# Monitoring_IC.net
KiCad netlist of a schematic drawn in Altium Designer
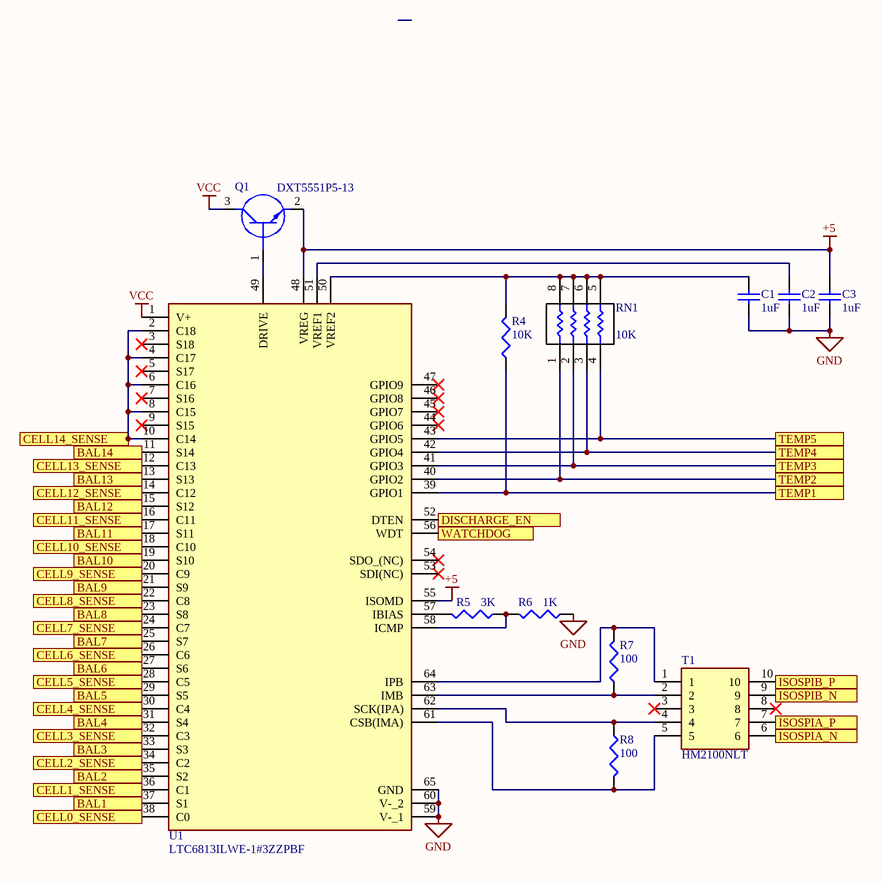
[diagram p0: Monitoring IC.SchDoc]

(export (version "E")
  (design (tool "Eeschema 10.0.6"))
  (components
    (comp (ref "C1")
      (value "1uF")
      (footprint "6-0805_N")
      (description "Capacitor")
      (fields (field (name "Comment") "Cap") (field (name "PUBLISHER") "Altium Limited"))
      (libsource (lib "Miscellaneous Devices") (part "Cap"))
    )
    (comp (ref "C2")
      (value "1uF")
      (footprint "6-0805_N")
      (description "Capacitor")
      (fields (field (name "Comment") "Cap") (field (name "PUBLISHER") "Altium Limited"))
      (libsource (lib "Miscellaneous Devices") (part "Cap"))
    )
    (comp (ref "C3")
      (value "1uF")
      (footprint "6-0805_N")
      (description "Capacitor")
      (fields (field (name "Comment") "Cap") (field (name "PUBLISHER") "Altium Limited"))
      (libsource (lib "Miscellaneous Devices") (part "Cap"))
    )
    (comp (ref "Q1")
      (value "DXT5551P5-13")
      (footprint "BMS Slave Device R1:DXT5551P513")
      (description "Transistor BJT NPN")
      (fields (field (name "MOUSER PART NUMBER") "522-DXT5551P5-13"))
      (libsource (lib "BMS Slave Device R1") (part "DXT5551P5-13"))
    )
    (comp (ref "R4")
      (value "10K")
      (footprint "J1-0603")
      (description "Resistor")
      (fields (field (name "Comment") "Res3") (field (name "PUBLISHER") "Altium Limited"))
      (libsource (lib "Miscellaneous Devices") (part "Res3"))
    )
    (comp (ref "R5")
      (value "3K")
      (footprint "J1-0603")
      (description "Resistor")
      (fields (field (name "Comment") "Res3") (field (name "PUBLISHER") "Altium Limited"))
      (libsource (lib "Miscellaneous Devices") (part "Res3"))
    )
    (comp (ref "R6")
      (value "1K")
      (footprint "J1-0603")
      (description "Resistor")
      (fields (field (name "Comment") "Res3") (field (name "PUBLISHER") "Altium Limited"))
      (libsource (lib "Miscellaneous Devices") (part "Res3"))
    )
    (comp (ref "R7")
      (value "100")
      (footprint "J1-0603")
      (description "Resistor")
      (fields (field (name "Comment") "Res3") (field (name "PUBLISHER") "Altium Limited"))
      (libsource (lib "Miscellaneous Devices") (part "Res3"))
    )
    (comp (ref "R8")
      (value "100")
      (footprint "J1-0603")
      (description "Resistor")
      (fields (field (name "Comment") "Res3") (field (name "PUBLISHER") "Altium Limited"))
      (libsource (lib "Miscellaneous Devices") (part "Res3"))
    )
    (comp (ref "RN1")
      (value "10K")
      (footprint "YC164")
      (description "Isolated Resistor Network")
      (fields (field (name "Comment") "Res Array") (field (name "PUBLISHER") "Altium Limited"))
      (libsource (lib "BMS Slave Device R1") (part "Res Array"))
    )
    (comp (ref "T1")
      (value "HM2100NLT")
      (footprint "HM2100NLT")
      (description "Transformer")
      (fields (field (name "MOUSER PART NUMBER") "673-HM2100NLT"))
      (libsource (lib "BMS Slave Device R1") (part "HM2100NLT"))
    )
    (comp (ref "U1")
      (value "LTC6813ILWE-1#3ZZPBF")
      (footprint "BMS Slave Device R1:QFP50P1200X1200X120-65N")
      (description "Integrated Circuit")
      (fields (field (name "MOUSER PART NUMBER") "584-6813ILWE13ZZPBF"))
      (libsource (lib "BMS Slave Device R1") (part "LTC6813ILWE-1#3ZZPBF"))
    )
  )
  (nets
    (net (code "1") (name "+5") (class "Default")
      (node (ref "C3") (pin "2") (pinfunction "2_2") (pintype "passive"))
      (node (ref "Q1") (pin "2") (pinfunction "E_2") (pintype "passive"))
      (node (ref "U1") (pin "48") (pinfunction "VREG_48") (pintype "passive"))
      (node (ref "U1") (pin "55") (pinfunction "ISOMD_55") (pintype "passive"))
    )
    (net (code "2") (name "/BAL1") (class "Default")
      (node (ref "U1") (pin "37") (pinfunction "S1_37") (pintype "passive"))
    )
    (net (code "3") (name "/BAL2") (class "Default")
      (node (ref "U1") (pin "35") (pinfunction "S2_35") (pintype "passive"))
    )
    (net (code "4") (name "/BAL3") (class "Default")
      (node (ref "U1") (pin "33") (pinfunction "S3_33") (pintype "passive"))
    )
    (net (code "5") (name "/BAL4") (class "Default")
      (node (ref "U1") (pin "31") (pinfunction "S4_31") (pintype "passive"))
    )
    (net (code "6") (name "/BAL5") (class "Default")
      (node (ref "U1") (pin "29") (pinfunction "S5_29") (pintype "passive"))
    )
    (net (code "7") (name "/BAL6") (class "Default")
      (node (ref "U1") (pin "27") (pinfunction "S6_27") (pintype "passive"))
    )
    (net (code "8") (name "/BAL7") (class "Default")
      (node (ref "U1") (pin "25") (pinfunction "S7_25") (pintype "passive"))
    )
    (net (code "9") (name "/BAL8") (class "Default")
      (node (ref "U1") (pin "23") (pinfunction "S8_23") (pintype "passive"))
    )
    (net (code "10") (name "/BAL9") (class "Default")
      (node (ref "U1") (pin "21") (pinfunction "S9_21") (pintype "passive"))
    )
    (net (code "11") (name "/BAL10") (class "Default")
      (node (ref "U1") (pin "19") (pinfunction "S10_19") (pintype "passive"))
    )
    (net (code "12") (name "/BAL11") (class "Default")
      (node (ref "U1") (pin "17") (pinfunction "S11_17") (pintype "passive"))
    )
    (net (code "13") (name "/BAL12") (class "Default")
      (node (ref "U1") (pin "15") (pinfunction "S12_15") (pintype "passive"))
    )
    (net (code "14") (name "/BAL13") (class "Default")
      (node (ref "U1") (pin "13") (pinfunction "S13_13") (pintype "passive"))
    )
    (net (code "15") (name "/BAL14") (class "Default")
      (node (ref "U1") (pin "11") (pinfunction "S14_11") (pintype "passive"))
    )
    (net (code "16") (name "/CELL0_SENSE") (class "Default")
      (node (ref "U1") (pin "38") (pinfunction "C0_38") (pintype "passive"))
    )
    (net (code "17") (name "/CELL1_SENSE") (class "Default")
      (node (ref "U1") (pin "36") (pinfunction "C1_36") (pintype "passive"))
    )
    (net (code "18") (name "/CELL2_SENSE") (class "Default")
      (node (ref "U1") (pin "34") (pinfunction "C2_34") (pintype "passive"))
    )
    (net (code "19") (name "/CELL3_SENSE") (class "Default")
      (node (ref "U1") (pin "32") (pinfunction "C3_32") (pintype "passive"))
    )
    (net (code "20") (name "/CELL4_SENSE") (class "Default")
      (node (ref "U1") (pin "30") (pinfunction "C4_30") (pintype "passive"))
    )
    (net (code "21") (name "/CELL5_SENSE") (class "Default")
      (node (ref "U1") (pin "28") (pinfunction "C5_28") (pintype "passive"))
    )
    (net (code "22") (name "/CELL6_SENSE") (class "Default")
      (node (ref "U1") (pin "26") (pinfunction "C6_26") (pintype "passive"))
    )
    (net (code "23") (name "/CELL7_SENSE") (class "Default")
      (node (ref "U1") (pin "24") (pinfunction "C7_24") (pintype "passive"))
    )
    (net (code "24") (name "/CELL8_SENSE") (class "Default")
      (node (ref "U1") (pin "22") (pinfunction "C8_22") (pintype "passive"))
    )
    (net (code "25") (name "/CELL9_SENSE") (class "Default")
      (node (ref "U1") (pin "20") (pinfunction "C9_20") (pintype "passive"))
    )
    (net (code "26") (name "/CELL10_SENSE") (class "Default")
      (node (ref "U1") (pin "18") (pinfunction "C10_18") (pintype "passive"))
    )
    (net (code "27") (name "/CELL11_SENSE") (class "Default")
      (node (ref "U1") (pin "16") (pinfunction "C11_16") (pintype "passive"))
    )
    (net (code "28") (name "/CELL12_SENSE") (class "Default")
      (node (ref "U1") (pin "14") (pinfunction "C12_14") (pintype "passive"))
    )
    (net (code "29") (name "/CELL13_SENSE") (class "Default")
      (node (ref "U1") (pin "12") (pinfunction "C13_12") (pintype "passive"))
    )
    (net (code "30") (name "/CELL14_SENSE") (class "Default")
      (node (ref "U1") (pin "10") (pinfunction "C14_10") (pintype "passive"))
      (node (ref "U1") (pin "2") (pinfunction "C18_2") (pintype "passive"))
      (node (ref "U1") (pin "4") (pinfunction "C17_4") (pintype "passive"))
      (node (ref "U1") (pin "6") (pinfunction "C16_6") (pintype "passive"))
      (node (ref "U1") (pin "8") (pinfunction "C15_8") (pintype "passive"))
    )
    (net (code "31") (name "/DISCHARGE_EN") (class "Default")
      (node (ref "U1") (pin "52") (pinfunction "DTEN_52") (pintype "passive"))
    )
    (net (code "32") (name "/ISOSPIA_N") (class "Default")
      (node (ref "T1") (pin "6") (pinfunction "6_6") (pintype "passive"))
    )
    (net (code "33") (name "/ISOSPIA_P") (class "Default")
      (node (ref "T1") (pin "7") (pinfunction "7_7") (pintype "passive"))
    )
    (net (code "34") (name "/ISOSPIB_N") (class "Default")
      (node (ref "T1") (pin "9") (pinfunction "9_9") (pintype "passive"))
    )
    (net (code "35") (name "/ISOSPIB_P") (class "Default")
      (node (ref "T1") (pin "10") (pinfunction "10_10") (pintype "passive"))
    )
    (net (code "36") (name "/TEMP1") (class "Default")
      (node (ref "R4") (pin "1") (pinfunction "1_1") (pintype "passive"))
      (node (ref "U1") (pin "39") (pinfunction "GPIO1_39") (pintype "passive"))
    )
    (net (code "37") (name "/TEMP2") (class "Default")
      (node (ref "RN1") (pin "1") (pinfunction "1_1") (pintype "passive"))
      (node (ref "U1") (pin "40") (pinfunction "GPIO2_40") (pintype "passive"))
    )
    (net (code "38") (name "/TEMP3") (class "Default")
      (node (ref "RN1") (pin "2") (pinfunction "2_2") (pintype "passive"))
      (node (ref "U1") (pin "41") (pinfunction "GPIO3_41") (pintype "passive"))
    )
    (net (code "39") (name "/TEMP4") (class "Default")
      (node (ref "RN1") (pin "3") (pinfunction "3_3") (pintype "passive"))
      (node (ref "U1") (pin "42") (pinfunction "GPIO4_42") (pintype "passive"))
    )
    (net (code "40") (name "/TEMP5") (class "Default")
      (node (ref "RN1") (pin "4") (pinfunction "4_4") (pintype "passive"))
      (node (ref "U1") (pin "43") (pinfunction "GPIO5_43") (pintype "passive"))
    )
    (net (code "41") (name "/WATCHDOG") (class "Default")
      (node (ref "U1") (pin "56") (pinfunction "WDT_56") (pintype "passive"))
    )
    (net (code "42") (name "GND") (class "Default")
      (node (ref "C1") (pin "1") (pinfunction "1_1") (pintype "passive"))
      (node (ref "C2") (pin "1") (pinfunction "1_1") (pintype "passive"))
      (node (ref "C3") (pin "1") (pinfunction "1_1") (pintype "passive"))
      (node (ref "R6") (pin "1") (pinfunction "1_1") (pintype "passive"))
      (node (ref "U1") (pin "59") (pinfunction "V-_1_59") (pintype "passive"))
      (node (ref "U1") (pin "60") (pinfunction "V-_2_60") (pintype "passive"))
      (node (ref "U1") (pin "65") (pinfunction "GND_65") (pintype "passive"))
    )
    (net (code "43") (name "Net-(Q1-B)") (class "Default")
      (node (ref "Q1") (pin "1") (pinfunction "B_1") (pintype "passive"))
      (node (ref "U1") (pin "49") (pinfunction "DRIVE_49") (pintype "passive"))
    )
    (net (code "44") (name "Net-(U1-CSB(IMA))") (class "Default")
      (node (ref "R8") (pin "2") (pinfunction "2_2") (pintype "passive"))
      (node (ref "T1") (pin "5") (pinfunction "5_5") (pintype "passive"))
      (node (ref "U1") (pin "61") (pinfunction "CSB(IMA)_61") (pintype "passive"))
    )
    (net (code "45") (name "Net-(U1-IBIAS)") (class "Default")
      (node (ref "R5") (pin "2") (pinfunction "2_2") (pintype "passive"))
      (node (ref "U1") (pin "57") (pinfunction "IBIAS_57") (pintype "passive"))
    )
    (net (code "46") (name "Net-(U1-ICMP)") (class "Default")
      (node (ref "R5") (pin "1") (pinfunction "1_1") (pintype "passive"))
      (node (ref "R6") (pin "2") (pinfunction "2_2") (pintype "passive"))
      (node (ref "U1") (pin "58") (pinfunction "ICMP_58") (pintype "passive"))
    )
    (net (code "47") (name "Net-(U1-IMB)") (class "Default")
      (node (ref "R7") (pin "1") (pinfunction "1_1") (pintype "passive"))
      (node (ref "T1") (pin "2") (pinfunction "2_2") (pintype "passive"))
      (node (ref "U1") (pin "63") (pinfunction "IMB_63") (pintype "passive"))
    )
    (net (code "48") (name "Net-(U1-IPB)") (class "Default")
      (node (ref "R7") (pin "2") (pinfunction "2_2") (pintype "passive"))
      (node (ref "T1") (pin "1") (pinfunction "1_1") (pintype "passive"))
      (node (ref "U1") (pin "64") (pinfunction "IPB_64") (pintype "passive"))
    )
    (net (code "49") (name "Net-(U1-SCK(IPA))") (class "Default")
      (node (ref "R8") (pin "1") (pinfunction "1_1") (pintype "passive"))
      (node (ref "T1") (pin "4") (pinfunction "4_4") (pintype "passive"))
      (node (ref "U1") (pin "62") (pinfunction "SCK(IPA)_62") (pintype "passive"))
    )
    (net (code "50") (name "Net-(U1-VREF1)") (class "Default")
      (node (ref "C2") (pin "2") (pinfunction "2_2") (pintype "passive"))
      (node (ref "U1") (pin "51") (pinfunction "VREF1_51") (pintype "passive"))
    )
    (net (code "51") (name "Net-(U1-VREF2)") (class "Default")
      (node (ref "C1") (pin "2") (pinfunction "2_2") (pintype "passive"))
      (node (ref "R4") (pin "2") (pinfunction "2_2") (pintype "passive"))
      (node (ref "RN1") (pin "5") (pinfunction "5_5") (pintype "passive"))
      (node (ref "RN1") (pin "6") (pinfunction "6_6") (pintype "passive"))
      (node (ref "RN1") (pin "7") (pinfunction "7_7") (pintype "passive"))
      (node (ref "RN1") (pin "8") (pinfunction "8_8") (pintype "passive"))
      (node (ref "U1") (pin "50") (pinfunction "VREF2_50") (pintype "passive"))
    )
    (net (code "52") (name "VCC") (class "Default")
      (node (ref "Q1") (pin "3") (pinfunction "C_3") (pintype "passive"))
      (node (ref "U1") (pin "1") (pinfunction "V+_1") (pintype "passive"))
    )
    (net (code "53") (name "unconnected-(T1-Pad3)") (class "Default")
      (node (ref "T1") (pin "3") (pinfunction "3_3") (pintype "passive+no_connect"))
    )
    (net (code "54") (name "unconnected-(T1-Pad8)") (class "Default")
      (node (ref "T1") (pin "8") (pinfunction "8_8") (pintype "passive+no_connect"))
    )
    (net (code "55") (name "unconnected-(U1-GPIO6-Pad44)") (class "Default")
      (node (ref "U1") (pin "44") (pinfunction "GPIO6_44") (pintype "passive+no_connect"))
    )
    (net (code "56") (name "unconnected-(U1-GPIO7-Pad45)") (class "Default")
      (node (ref "U1") (pin "45") (pinfunction "GPIO7_45") (pintype "passive+no_connect"))
    )
    (net (code "57") (name "unconnected-(U1-GPIO8-Pad46)") (class "Default")
      (node (ref "U1") (pin "46") (pinfunction "GPIO8_46") (pintype "passive+no_connect"))
    )
    (net (code "58") (name "unconnected-(U1-GPIO9-Pad47)") (class "Default")
      (node (ref "U1") (pin "47") (pinfunction "GPIO9_47") (pintype "passive+no_connect"))
    )
    (net (code "59") (name "unconnected-(U1-S15-Pad9)") (class "Default")
      (node (ref "U1") (pin "9") (pinfunction "S15_9") (pintype "passive+no_connect"))
    )
    (net (code "60") (name "unconnected-(U1-S16-Pad7)") (class "Default")
      (node (ref "U1") (pin "7") (pinfunction "S16_7") (pintype "passive+no_connect"))
    )
    (net (code "61") (name "unconnected-(U1-S17-Pad5)") (class "Default")
      (node (ref "U1") (pin "5") (pinfunction "S17_5") (pintype "passive+no_connect"))
    )
    (net (code "62") (name "unconnected-(U1-S18-Pad3)") (class "Default")
      (node (ref "U1") (pin "3") (pinfunction "S18_3") (pintype "passive+no_connect"))
    )
    (net (code "63") (name "unconnected-(U1-SDI(NC)-Pad53)") (class "Default")
      (node (ref "U1") (pin "53") (pinfunction "SDI(NC)_53") (pintype "passive+no_connect"))
    )
    (net (code "64") (name "unconnected-(U1-SDO_(NC)-Pad54)") (class "Default")
      (node (ref "U1") (pin "54") (pinfunction "SDO_(NC)_54") (pintype "passive+no_connect"))
    )
  )
)
